# AB2KController.net
KiCad netlist of a schematic drawn in EAGLE
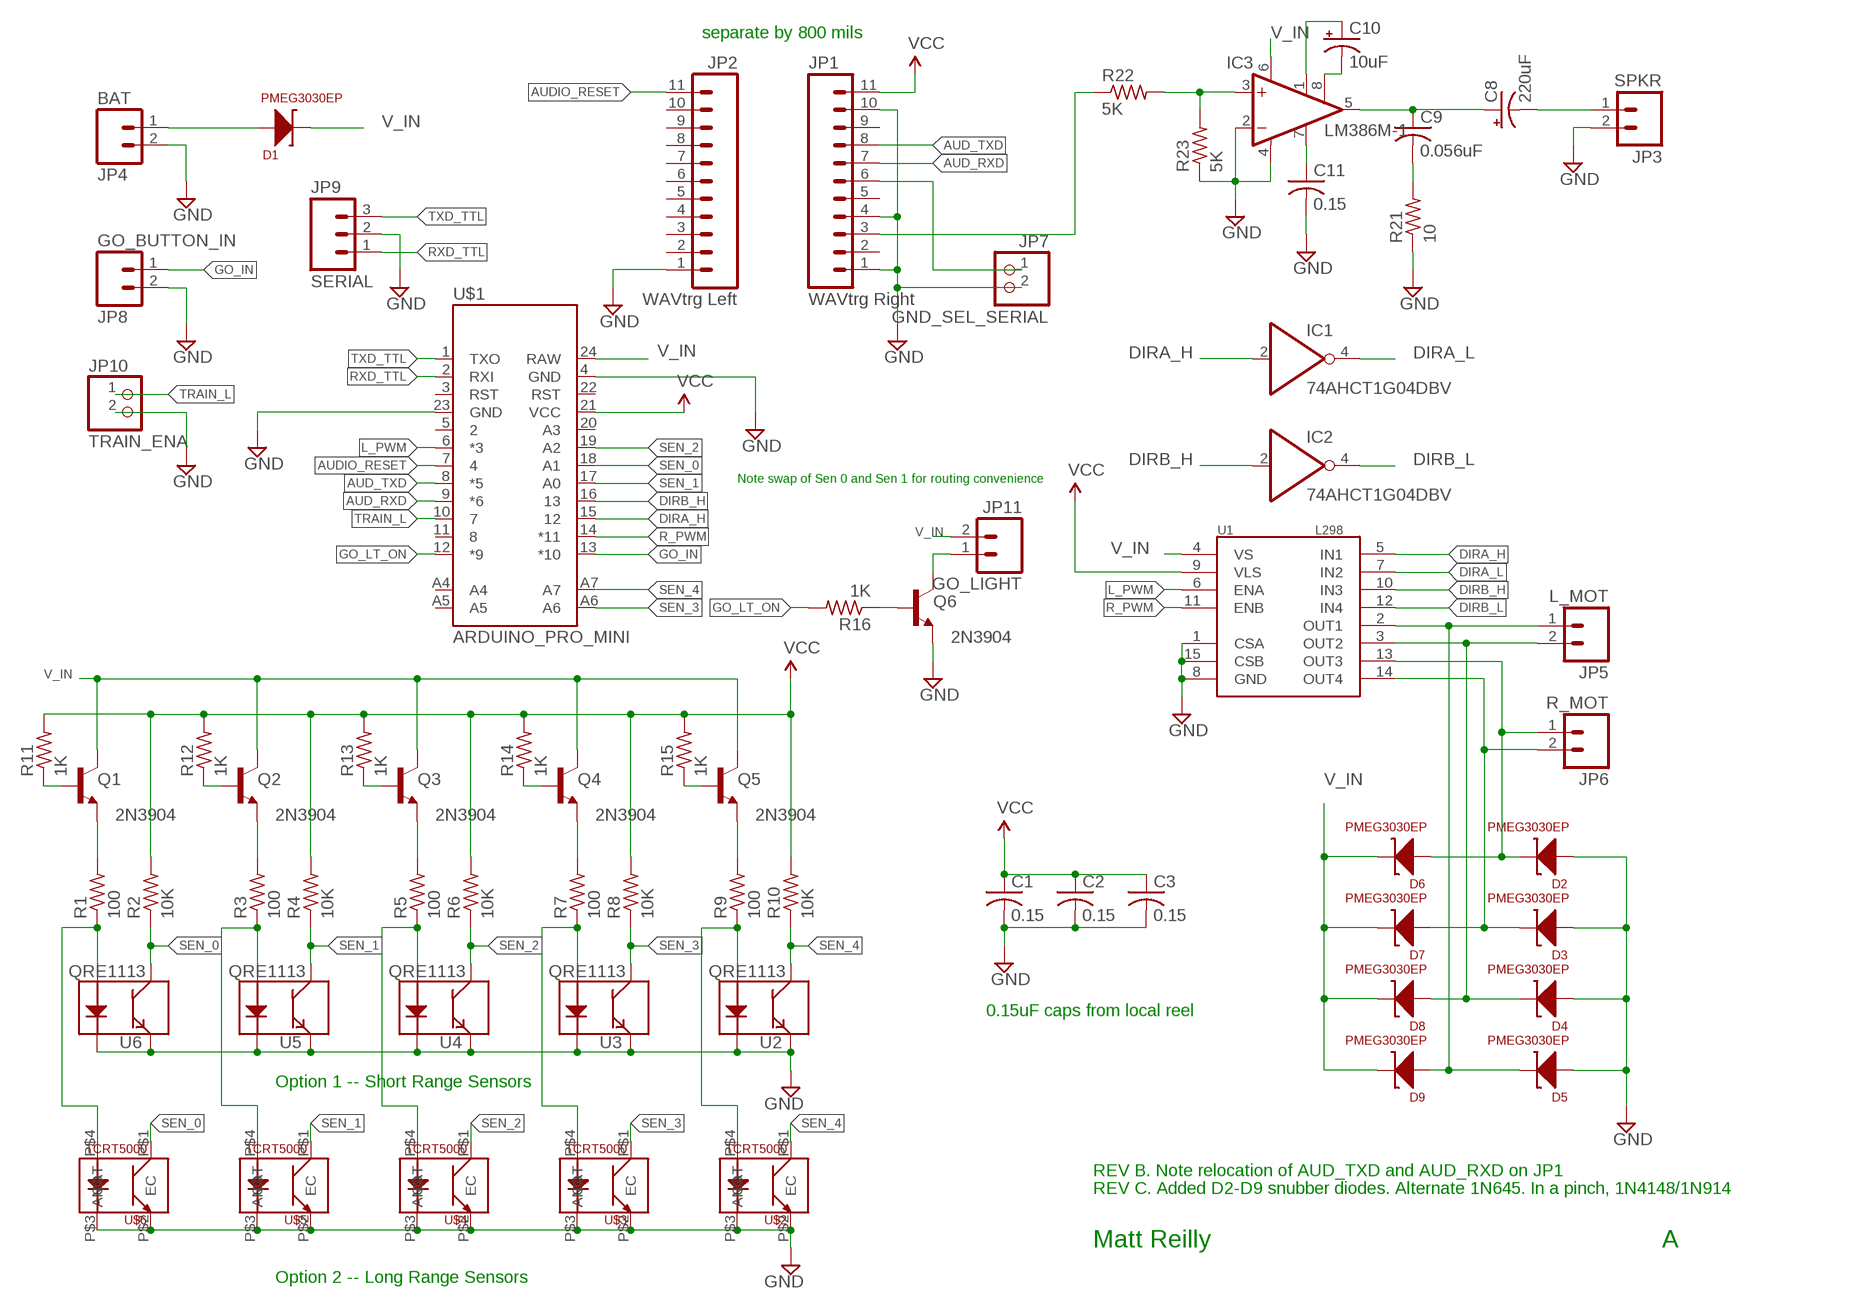
[diagram p0: schematic, sheet 1]

(export (version "E")
  (design (tool "Eeschema 10.0.6"))
  (components
    (comp (ref "C1")
      (value "0.15")
      (footprint "eagle-import:C1206K")
      (libsource (lib "eagle-import") (part "resistor_C-USC1206K"))
    )
    (comp (ref "C2")
      (value "0.15")
      (footprint "eagle-import:C1206K")
      (libsource (lib "eagle-import") (part "resistor_C-USC1206K"))
    )
    (comp (ref "C3")
      (value "0.15")
      (footprint "eagle-import:C1206K")
      (libsource (lib "eagle-import") (part "resistor_C-USC1206K"))
    )
    (comp (ref "C8")
      (value "220uF")
      (footprint "eagle-import:D_7343-31R")
      (libsource (lib "eagle-import") (part "CPOL-USD/7343-31R"))
    )
    (comp (ref "C9")
      (value "0.056uF")
      (footprint "eagle-import:C1210")
      (libsource (lib "eagle-import") (part "C-USC1210"))
    )
    (comp (ref "C10")
      (value "10uF")
      (footprint "eagle-import:D_7343-31R")
      (libsource (lib "eagle-import") (part "CPOL-USD/7343-31R"))
    )
    (comp (ref "C11")
      (value "0.15")
      (footprint "eagle-import:C1206K")
      (libsource (lib "eagle-import") (part "resistor_C-USC1206K"))
    )
    (comp (ref "D1")
      (value "PMEG3030EP")
      (footprint "eagle-import:SOD128")
      (libsource (lib "eagle-import") (part "PMEG3030EP"))
    )
    (comp (ref "D2")
      (value "PMEG3030EP")
      (footprint "eagle-import:SOD128")
      (libsource (lib "eagle-import") (part "PMEG3030EP"))
    )
    (comp (ref "D3")
      (value "PMEG3030EP")
      (footprint "eagle-import:SOD128")
      (libsource (lib "eagle-import") (part "PMEG3030EP"))
    )
    (comp (ref "D4")
      (value "PMEG3030EP")
      (footprint "eagle-import:SOD128")
      (libsource (lib "eagle-import") (part "PMEG3030EP"))
    )
    (comp (ref "D5")
      (value "PMEG3030EP")
      (footprint "eagle-import:SOD128")
      (libsource (lib "eagle-import") (part "PMEG3030EP"))
    )
    (comp (ref "D6")
      (value "PMEG3030EP")
      (footprint "eagle-import:SOD128")
      (libsource (lib "eagle-import") (part "PMEG3030EP"))
    )
    (comp (ref "D7")
      (value "PMEG3030EP")
      (footprint "eagle-import:SOD128")
      (libsource (lib "eagle-import") (part "PMEG3030EP"))
    )
    (comp (ref "D8")
      (value "PMEG3030EP")
      (footprint "eagle-import:SOD128")
      (libsource (lib "eagle-import") (part "PMEG3030EP"))
    )
    (comp (ref "D9")
      (value "PMEG3030EP")
      (footprint "eagle-import:SOD128")
      (libsource (lib "eagle-import") (part "PMEG3030EP"))
    )
    (comp (ref "IC1")
      (value "74AHCT1G04DBV")
      (footprint "eagle-import:SOT23-5")
      (libsource (lib "eagle-import") (part "741G04DBVAHCT"))
    )
    (comp (ref "IC2")
      (value "74AHCT1G04DBV")
      (footprint "eagle-import:SOT23-5")
      (libsource (lib "eagle-import") (part "741G04DBVAHCT"))
    )
    (comp (ref "IC3")
      (value "LM386M-1")
      (footprint "eagle-import:SO08")
      (libsource (lib "eagle-import") (part "LM386?-M1"))
    )
    (comp (ref "JP1")
      (value "WAVtrg Right")
      (footprint "eagle-import:1X11")
      (libsource (lib "eagle-import") (part "M11PTH"))
    )
    (comp (ref "JP2")
      (value "WAVtrg Left")
      (footprint "eagle-import:1X11")
      (libsource (lib "eagle-import") (part "M11PTH"))
    )
    (comp (ref "JP3")
      (value "SPKR")
      (footprint "eagle-import:SCREWTERMINAL-5MM-2")
      (libsource (lib "eagle-import") (part "M025MM"))
    )
    (comp (ref "JP4")
      (value "BAT")
      (footprint "eagle-import:SCREWTERMINAL-5MM-2")
      (libsource (lib "eagle-import") (part "M025MM"))
    )
    (comp (ref "JP5")
      (value "L_MOT")
      (footprint "eagle-import:SCREWTERMINAL-5MM-2")
      (libsource (lib "eagle-import") (part "M025MM"))
    )
    (comp (ref "JP6")
      (value "R_MOT")
      (footprint "eagle-import:SCREWTERMINAL-5MM-2")
      (libsource (lib "eagle-import") (part "M025MM"))
    )
    (comp (ref "JP7")
      (value "GND_SEL_SERIAL")
      (footprint "eagle-import:1X02")
      (libsource (lib "eagle-import") (part "PINHD-1X2"))
    )
    (comp (ref "JP8")
      (value "GO_BUTTON_IN")
      (footprint "eagle-import:SCREWTERMINAL-5MM-2")
      (libsource (lib "eagle-import") (part "M025MM"))
    )
    (comp (ref "JP9")
      (value "SERIAL")
      (footprint "eagle-import:1X03")
      (libsource (lib "eagle-import") (part "M03PTH"))
    )
    (comp (ref "JP10")
      (value "TRAIN_ENA")
      (footprint "eagle-import:1X02")
      (libsource (lib "eagle-import") (part "PINHD-1X2"))
    )
    (comp (ref "JP11")
      (value "GO_LIGHT")
      (footprint "eagle-import:SCREWTERMINAL-5MM-2")
      (libsource (lib "eagle-import") (part "M025MM"))
    )
    (comp (ref "Q1")
      (value "2N3904")
      (footprint "eagle-import:TO92")
      (libsource (lib "eagle-import") (part "2N3904"))
    )
    (comp (ref "Q2")
      (value "2N3904")
      (footprint "eagle-import:TO92")
      (libsource (lib "eagle-import") (part "2N3904"))
    )
    (comp (ref "Q3")
      (value "2N3904")
      (footprint "eagle-import:TO92")
      (libsource (lib "eagle-import") (part "2N3904"))
    )
    (comp (ref "Q4")
      (value "2N3904")
      (footprint "eagle-import:TO92")
      (libsource (lib "eagle-import") (part "2N3904"))
    )
    (comp (ref "Q5")
      (value "2N3904")
      (footprint "eagle-import:TO92")
      (libsource (lib "eagle-import") (part "2N3904"))
    )
    (comp (ref "Q6")
      (value "2N3904")
      (footprint "eagle-import:TO92")
      (libsource (lib "eagle-import") (part "2N3904"))
    )
    (comp (ref "R1")
      (value "100")
      (footprint "eagle-import:M1206")
      (libsource (lib "eagle-import") (part "resistor_R-US_M1206"))
    )
    (comp (ref "R2")
      (value "10K")
      (footprint "eagle-import:M1206")
      (libsource (lib "eagle-import") (part "resistor_R-US_M1206"))
    )
    (comp (ref "R3")
      (value "100")
      (footprint "eagle-import:M1206")
      (libsource (lib "eagle-import") (part "resistor_R-US_M1206"))
    )
    (comp (ref "R4")
      (value "10K")
      (footprint "eagle-import:M1206")
      (libsource (lib "eagle-import") (part "resistor_R-US_M1206"))
    )
    (comp (ref "R5")
      (value "100")
      (footprint "eagle-import:M1206")
      (libsource (lib "eagle-import") (part "resistor_R-US_M1206"))
    )
    (comp (ref "R6")
      (value "10K")
      (footprint "eagle-import:M1206")
      (libsource (lib "eagle-import") (part "resistor_R-US_M1206"))
    )
    (comp (ref "R7")
      (value "100")
      (footprint "eagle-import:M1206")
      (libsource (lib "eagle-import") (part "resistor_R-US_M1206"))
    )
    (comp (ref "R8")
      (value "10K")
      (footprint "eagle-import:M1206")
      (libsource (lib "eagle-import") (part "resistor_R-US_M1206"))
    )
    (comp (ref "R9")
      (value "100")
      (footprint "eagle-import:M1206")
      (libsource (lib "eagle-import") (part "resistor_R-US_M1206"))
    )
    (comp (ref "R10")
      (value "10K")
      (footprint "eagle-import:M1206")
      (libsource (lib "eagle-import") (part "resistor_R-US_M1206"))
    )
    (comp (ref "R11")
      (value "1K")
      (footprint "eagle-import:M1206")
      (libsource (lib "eagle-import") (part "resistor_R-US_M1206"))
    )
    (comp (ref "R12")
      (value "1K")
      (footprint "eagle-import:M1206")
      (libsource (lib "eagle-import") (part "resistor_R-US_M1206"))
    )
    (comp (ref "R13")
      (value "1K")
      (footprint "eagle-import:M1206")
      (libsource (lib "eagle-import") (part "resistor_R-US_M1206"))
    )
    (comp (ref "R14")
      (value "1K")
      (footprint "eagle-import:M1206")
      (libsource (lib "eagle-import") (part "resistor_R-US_M1206"))
    )
    (comp (ref "R15")
      (value "1K")
      (footprint "eagle-import:M1206")
      (libsource (lib "eagle-import") (part "resistor_R-US_M1206"))
    )
    (comp (ref "R16")
      (value "1K")
      (footprint "eagle-import:M1206")
      (libsource (lib "eagle-import") (part "resistor_R-US_M1206"))
    )
    (comp (ref "R21")
      (value "10")
      (footprint "eagle-import:R1210")
      (libsource (lib "eagle-import") (part "R-US_R1210"))
    )
    (comp (ref "R22")
      (value "5K")
      (footprint "eagle-import:R1206")
      (libsource (lib "eagle-import") (part "R-US_R1206"))
    )
    (comp (ref "R23")
      (value "5K")
      (footprint "eagle-import:R1206")
      (libsource (lib "eagle-import") (part "R-US_R1206"))
    )
    (comp (ref "U$1")
      (value "ARDUINO_PRO_MINI")
      (footprint "eagle-import:ARDUINO_PRO_MINI")
      (libsource (lib "eagle-import") (part "ARDUINO_PRO_MINI"))
    )
    (comp (ref "U$2")
      (value "TCRT5000")
      (footprint "eagle-import:TCRT5000")
      (libsource (lib "eagle-import") (part "TCRT5000"))
    )
    (comp (ref "U$3")
      (value "TCRT5000")
      (footprint "eagle-import:TCRT5000")
      (libsource (lib "eagle-import") (part "TCRT5000"))
    )
    (comp (ref "U$4")
      (value "TCRT5000")
      (footprint "eagle-import:TCRT5000")
      (libsource (lib "eagle-import") (part "TCRT5000"))
    )
    (comp (ref "U$5")
      (value "TCRT5000")
      (footprint "eagle-import:TCRT5000")
      (libsource (lib "eagle-import") (part "TCRT5000"))
    )
    (comp (ref "U$6")
      (value "TCRT5000")
      (footprint "eagle-import:TCRT5000")
      (libsource (lib "eagle-import") (part "TCRT5000"))
    )
    (comp (ref "U1")
      (value "L298")
      (footprint "eagle-import:MULTIWATT15")
      (libsource (lib "eagle-import") (part "L298"))
    )
    (comp (ref "U2")
      (value "QRE1113")
      (footprint "eagle-import:QRE1113")
      (libsource (lib "eagle-import") (part "QRE1113"))
    )
    (comp (ref "U3")
      (value "QRE1113")
      (footprint "eagle-import:QRE1113")
      (libsource (lib "eagle-import") (part "QRE1113"))
    )
    (comp (ref "U4")
      (value "QRE1113")
      (footprint "eagle-import:QRE1113")
      (libsource (lib "eagle-import") (part "QRE1113"))
    )
    (comp (ref "U5")
      (value "QRE1113")
      (footprint "eagle-import:QRE1113")
      (libsource (lib "eagle-import") (part "QRE1113"))
    )
    (comp (ref "U6")
      (value "QRE1113")
      (footprint "eagle-import:QRE1113")
      (libsource (lib "eagle-import") (part "QRE1113"))
    )
  )
  (nets
    (net (code "1") (name "/V_IN") (class "Default")
      (node (ref "D1") (pin "P$2") (pinfunction "C_P$2") (pintype "bidirectional"))
      (node (ref "D6") (pin "P$2") (pinfunction "C_P$2") (pintype "bidirectional"))
      (node (ref "D7") (pin "P$2") (pinfunction "C_P$2") (pintype "bidirectional"))
      (node (ref "D8") (pin "P$2") (pinfunction "C_P$2") (pintype "bidirectional"))
      (node (ref "D9") (pin "P$2") (pinfunction "C_P$2") (pintype "bidirectional"))
      (node (ref "IC3") (pin "6") (pinfunction "VS_6") (pintype "power_in"))
      (node (ref "JP11") (pin "2") (pinfunction "2_2") (pintype "passive"))
      (node (ref "Q1") (pin "1") (pinfunction "C_1") (pintype "passive"))
      (node (ref "Q2") (pin "1") (pinfunction "C_1") (pintype "passive"))
      (node (ref "Q3") (pin "1") (pinfunction "C_1") (pintype "passive"))
      (node (ref "Q4") (pin "1") (pinfunction "C_1") (pintype "passive"))
      (node (ref "Q5") (pin "1") (pinfunction "C_1") (pintype "passive"))
      (node (ref "U$1") (pin "24") (pinfunction "RAW_24") (pintype "bidirectional"))
      (node (ref "U1") (pin "4") (pinfunction "VS_4") (pintype "bidirectional"))
    )
    (net (code "2") (name "AUDIO_RESET") (class "Default")
      (node (ref "JP2") (pin "11") (pinfunction "11_11") (pintype "passive"))
      (node (ref "U$1") (pin "7") (pinfunction "4_7") (pintype "bidirectional"))
    )
    (net (code "3") (name "AUD_RXD") (class "Default")
      (node (ref "JP1") (pin "7") (pinfunction "7_7") (pintype "passive"))
      (node (ref "U$1") (pin "9") (pinfunction "*6_9") (pintype "bidirectional"))
    )
    (net (code "4") (name "AUD_TXD") (class "Default")
      (node (ref "JP1") (pin "8") (pinfunction "8_8") (pintype "passive"))
      (node (ref "U$1") (pin "8") (pinfunction "*5_8") (pintype "bidirectional"))
    )
    (net (code "5") (name "DIRA_H") (class "Default")
      (node (ref "IC1") (pin "2") (pinfunction "I_2") (pintype "input"))
      (node (ref "U$1") (pin "15") (pinfunction "12_15") (pintype "bidirectional"))
      (node (ref "U1") (pin "5") (pinfunction "IN1_5") (pintype "bidirectional"))
    )
    (net (code "6") (name "DIRA_L") (class "Default")
      (node (ref "IC1") (pin "4") (pinfunction "O_4") (pintype "output"))
      (node (ref "U1") (pin "7") (pinfunction "IN2_7") (pintype "bidirectional"))
    )
    (net (code "7") (name "DIRB_H") (class "Default")
      (node (ref "IC2") (pin "2") (pinfunction "I_2") (pintype "input"))
      (node (ref "U$1") (pin "16") (pinfunction "13_16") (pintype "bidirectional"))
      (node (ref "U1") (pin "10") (pinfunction "IN3_10") (pintype "bidirectional"))
    )
    (net (code "8") (name "DIRB_L") (class "Default")
      (node (ref "IC2") (pin "4") (pinfunction "O_4") (pintype "output"))
      (node (ref "U1") (pin "12") (pinfunction "IN4_12") (pintype "bidirectional"))
    )
    (net (code "9") (name "GND") (class "Default")
      (node (ref "C1") (pin "2") (pinfunction "2_2") (pintype "passive"))
      (node (ref "C11") (pin "2") (pinfunction "2_2") (pintype "passive"))
      (node (ref "C2") (pin "2") (pinfunction "2_2") (pintype "passive"))
      (node (ref "C3") (pin "2") (pinfunction "2_2") (pintype "passive"))
      (node (ref "D2") (pin "P$1") (pinfunction "A_P$1") (pintype "bidirectional"))
      (node (ref "D3") (pin "P$1") (pinfunction "A_P$1") (pintype "bidirectional"))
      (node (ref "D4") (pin "P$1") (pinfunction "A_P$1") (pintype "bidirectional"))
      (node (ref "D5") (pin "P$1") (pinfunction "A_P$1") (pintype "bidirectional"))
      (node (ref "IC3") (pin "2") (pinfunction "-IN_2") (pintype "input"))
      (node (ref "IC3") (pin "4") (pinfunction "GND_4") (pintype "power_in"))
      (node (ref "JP1") (pin "1") (pinfunction "1_1") (pintype "passive"))
      (node (ref "JP1") (pin "10") (pinfunction "10_10") (pintype "passive"))
      (node (ref "JP1") (pin "4") (pinfunction "4_4") (pintype "passive"))
      (node (ref "JP10") (pin "2") (pinfunction "2_2") (pintype "passive"))
      (node (ref "JP2") (pin "1") (pinfunction "1_1") (pintype "passive"))
      (node (ref "JP3") (pin "2") (pinfunction "2_2") (pintype "passive"))
      (node (ref "JP4") (pin "2") (pinfunction "2_2") (pintype "passive"))
      (node (ref "JP7") (pin "2") (pinfunction "2_2") (pintype "passive"))
      (node (ref "JP8") (pin "2") (pinfunction "2_2") (pintype "passive"))
      (node (ref "JP9") (pin "2") (pinfunction "2_2") (pintype "passive"))
      (node (ref "Q6") (pin "3") (pinfunction "E_3") (pintype "passive"))
      (node (ref "R21") (pin "1") (pinfunction "1_1") (pintype "passive"))
      (node (ref "R23") (pin "1") (pinfunction "1_1") (pintype "passive"))
      (node (ref "U$1") (pin "23") (pinfunction "GND_23") (pintype "bidirectional"))
      (node (ref "U$1") (pin "4") (pinfunction "GND_4") (pintype "bidirectional"))
      (node (ref "U$2") (pin "P$2") (pinfunction "E_P$2") (pintype "bidirectional"))
      (node (ref "U$2") (pin "P$3") (pinfunction "CAT_P$3") (pintype "bidirectional"))
      (node (ref "U$3") (pin "P$2") (pinfunction "E_P$2") (pintype "bidirectional"))
      (node (ref "U$3") (pin "P$3") (pinfunction "CAT_P$3") (pintype "bidirectional"))
      (node (ref "U$4") (pin "P$2") (pinfunction "E_P$2") (pintype "bidirectional"))
      (node (ref "U$4") (pin "P$3") (pinfunction "CAT_P$3") (pintype "bidirectional"))
      (node (ref "U$5") (pin "P$2") (pinfunction "E_P$2") (pintype "bidirectional"))
      (node (ref "U$5") (pin "P$3") (pinfunction "CAT_P$3") (pintype "bidirectional"))
      (node (ref "U$6") (pin "P$2") (pinfunction "E_P$2") (pintype "bidirectional"))
      (node (ref "U$6") (pin "P$3") (pinfunction "CAT_P$3") (pintype "bidirectional"))
      (node (ref "U1") (pin "1") (pinfunction "CSA_1") (pintype "bidirectional"))
      (node (ref "U1") (pin "15") (pinfunction "CSB_15") (pintype "bidirectional"))
      (node (ref "U1") (pin "8") (pinfunction "GND_8") (pintype "bidirectional"))
      (node (ref "U2") (pin "2") (pinfunction "K_2") (pintype "bidirectional"))
      (node (ref "U2") (pin "4") (pinfunction "E_4") (pintype "bidirectional"))
      (node (ref "U3") (pin "2") (pinfunction "K_2") (pintype "bidirectional"))
      (node (ref "U3") (pin "4") (pinfunction "E_4") (pintype "bidirectional"))
      (node (ref "U4") (pin "2") (pinfunction "K_2") (pintype "bidirectional"))
      (node (ref "U4") (pin "4") (pinfunction "E_4") (pintype "bidirectional"))
      (node (ref "U5") (pin "2") (pinfunction "K_2") (pintype "bidirectional"))
      (node (ref "U5") (pin "4") (pinfunction "E_4") (pintype "bidirectional"))
      (node (ref "U6") (pin "2") (pinfunction "K_2") (pintype "bidirectional"))
      (node (ref "U6") (pin "4") (pinfunction "E_4") (pintype "bidirectional"))
    )
    (net (code "10") (name "GO_IN") (class "Default")
      (node (ref "JP8") (pin "1") (pinfunction "1_1") (pintype "passive"))
      (node (ref "U$1") (pin "13") (pinfunction "*10_13") (pintype "bidirectional"))
    )
    (net (code "11") (name "GO_LT_ON") (class "Default")
      (node (ref "R16") (pin "2") (pinfunction "2_2") (pintype "passive"))
      (node (ref "U$1") (pin "12") (pinfunction "*9_12") (pintype "bidirectional"))
    )
    (net (code "12") (name "L_PWM") (class "Default")
      (node (ref "U$1") (pin "6") (pinfunction "*3_6") (pintype "bidirectional"))
      (node (ref "U1") (pin "6") (pinfunction "ENA_6") (pintype "bidirectional"))
    )
    (net (code "13") (name "Net-(C8-Pad-)") (class "Default")
      (node (ref "C8") (pin "-") (pinfunction "-_-") (pintype "passive"))
      (node (ref "JP3") (pin "1") (pinfunction "1_1") (pintype "passive"))
    )
    (net (code "14") (name "Net-(C9-Pad2)") (class "Default")
      (node (ref "C9") (pin "2") (pinfunction "2_2") (pintype "passive"))
      (node (ref "R21") (pin "2") (pinfunction "2_2") (pintype "passive"))
    )
    (net (code "15") (name "Net-(C10-Pad+)") (class "Default")
      (node (ref "C10") (pin "+") (pinfunction "+_+") (pintype "passive"))
      (node (ref "IC3") (pin "1") (pinfunction "GAIN_1") (pintype "passive"))
    )
    (net (code "16") (name "Net-(C10-Pad-)") (class "Default")
      (node (ref "C10") (pin "-") (pinfunction "-_-") (pintype "passive"))
      (node (ref "IC3") (pin "8") (pinfunction "GAIN_8") (pintype "passive"))
    )
    (net (code "17") (name "Net-(D1-A)") (class "Default")
      (node (ref "D1") (pin "P$1") (pinfunction "A_P$1") (pintype "bidirectional"))
      (node (ref "JP4") (pin "1") (pinfunction "1_1") (pintype "passive"))
    )
    (net (code "18") (name "Net-(D2-C)") (class "Default")
      (node (ref "D2") (pin "P$2") (pinfunction "C_P$2") (pintype "bidirectional"))
      (node (ref "D6") (pin "P$1") (pinfunction "A_P$1") (pintype "bidirectional"))
      (node (ref "JP6") (pin "1") (pinfunction "1_1") (pintype "passive"))
      (node (ref "U1") (pin "13") (pinfunction "OUT3_13") (pintype "bidirectional"))
    )
    (net (code "19") (name "Net-(D3-C)") (class "Default")
      (node (ref "D3") (pin "P$2") (pinfunction "C_P$2") (pintype "bidirectional"))
      (node (ref "D7") (pin "P$1") (pinfunction "A_P$1") (pintype "bidirectional"))
      (node (ref "JP6") (pin "2") (pinfunction "2_2") (pintype "passive"))
      (node (ref "U1") (pin "14") (pinfunction "OUT4_14") (pintype "bidirectional"))
    )
    (net (code "20") (name "Net-(D4-C)") (class "Default")
      (node (ref "D4") (pin "P$2") (pinfunction "C_P$2") (pintype "bidirectional"))
      (node (ref "D8") (pin "P$1") (pinfunction "A_P$1") (pintype "bidirectional"))
      (node (ref "JP5") (pin "2") (pinfunction "2_2") (pintype "passive"))
      (node (ref "U1") (pin "3") (pinfunction "OUT2_3") (pintype "bidirectional"))
    )
    (net (code "21") (name "Net-(D5-C)") (class "Default")
      (node (ref "D5") (pin "P$2") (pinfunction "C_P$2") (pintype "bidirectional"))
      (node (ref "D9") (pin "P$1") (pinfunction "A_P$1") (pintype "bidirectional"))
      (node (ref "JP5") (pin "1") (pinfunction "1_1") (pintype "passive"))
      (node (ref "U1") (pin "2") (pinfunction "OUT1_2") (pintype "bidirectional"))
    )
    (net (code "22") (name "Net-(IC3-+IN)") (class "Default")
      (node (ref "IC3") (pin "3") (pinfunction "+IN_3") (pintype "input"))
      (node (ref "R22") (pin "2") (pinfunction "2_2") (pintype "passive"))
      (node (ref "R23") (pin "2") (pinfunction "2_2") (pintype "passive"))
    )
    (net (code "23") (name "Net-(IC3-BYPASS)") (class "Default")
      (node (ref "C11") (pin "1") (pinfunction "1_1") (pintype "passive"))
      (node (ref "IC3") (pin "7") (pinfunction "BYPASS_7") (pintype "passive"))
    )
    (net (code "24") (name "Net-(IC3-OUT)") (class "Default")
      (node (ref "C8") (pin "+") (pinfunction "+_+") (pintype "passive"))
      (node (ref "C9") (pin "1") (pinfunction "1_1") (pintype "passive"))
      (node (ref "IC3") (pin "5") (pinfunction "OUT_5") (pintype "output"))
    )
    (net (code "25") (name "Net-(JP1-Pad3)") (class "Default")
      (node (ref "JP1") (pin "3") (pinfunction "3_3") (pintype "passive"))
      (node (ref "R22") (pin "1") (pinfunction "1_1") (pintype "passive"))
    )
    (net (code "26") (name "Net-(JP1-Pad6)") (class "Default")
      (node (ref "JP1") (pin "6") (pinfunction "6_6") (pintype "passive"))
      (node (ref "JP7") (pin "1") (pinfunction "1_1") (pintype "passive"))
    )
    (net (code "27") (name "Net-(Q1-B)") (class "Default")
      (node (ref "Q1") (pin "2") (pinfunction "B_2") (pintype "passive"))
      (node (ref "R11") (pin "1") (pinfunction "1_1") (pintype "passive"))
    )
    (net (code "28") (name "Net-(Q1-E)") (class "Default")
      (node (ref "Q1") (pin "3") (pinfunction "E_3") (pintype "passive"))
      (node (ref "R1") (pin "2") (pinfunction "2_2") (pintype "passive"))
    )
    (net (code "29") (name "Net-(Q2-B)") (class "Default")
      (node (ref "Q2") (pin "2") (pinfunction "B_2") (pintype "passive"))
      (node (ref "R12") (pin "1") (pinfunction "1_1") (pintype "passive"))
    )
    (net (code "30") (name "Net-(Q2-E)") (class "Default")
      (node (ref "Q2") (pin "3") (pinfunction "E_3") (pintype "passive"))
      (node (ref "R3") (pin "2") (pinfunction "2_2") (pintype "passive"))
    )
    (net (code "31") (name "Net-(Q3-B)") (class "Default")
      (node (ref "Q3") (pin "2") (pinfunction "B_2") (pintype "passive"))
      (node (ref "R13") (pin "1") (pinfunction "1_1") (pintype "passive"))
    )
    (net (code "32") (name "Net-(Q3-E)") (class "Default")
      (node (ref "Q3") (pin "3") (pinfunction "E_3") (pintype "passive"))
      (node (ref "R5") (pin "2") (pinfunction "2_2") (pintype "passive"))
    )
    (net (code "33") (name "Net-(Q4-B)") (class "Default")
      (node (ref "Q4") (pin "2") (pinfunction "B_2") (pintype "passive"))
      (node (ref "R14") (pin "1") (pinfunction "1_1") (pintype "passive"))
    )
    (net (code "34") (name "Net-(Q4-E)") (class "Default")
      (node (ref "Q4") (pin "3") (pinfunction "E_3") (pintype "passive"))
      (node (ref "R7") (pin "2") (pinfunction "2_2") (pintype "passive"))
    )
    (net (code "35") (name "Net-(Q5-B)") (class "Default")
      (node (ref "Q5") (pin "2") (pinfunction "B_2") (pintype "passive"))
      (node (ref "R15") (pin "1") (pinfunction "1_1") (pintype "passive"))
    )
    (net (code "36") (name "Net-(Q5-E)") (class "Default")
      (node (ref "Q5") (pin "3") (pinfunction "E_3") (pintype "passive"))
      (node (ref "R9") (pin "2") (pinfunction "2_2") (pintype "passive"))
    )
    (net (code "37") (name "Net-(Q6-B)") (class "Default")
      (node (ref "Q6") (pin "2") (pinfunction "B_2") (pintype "passive"))
      (node (ref "R16") (pin "1") (pinfunction "1_1") (pintype "passive"))
    )
    (net (code "38") (name "Net-(Q6-C)") (class "Default")
      (node (ref "JP11") (pin "1") (pinfunction "1_1") (pintype "passive"))
      (node (ref "Q6") (pin "1") (pinfunction "C_1") (pintype "passive"))
    )
    (net (code "39") (name "Net-(U$2-ANO)") (class "Default")
      (node (ref "R9") (pin "1") (pinfunction "1_1") (pintype "passive"))
      (node (ref "U$2") (pin "P$4") (pinfunction "ANO_P$4") (pintype "bidirectional"))
      (node (ref "U2") (pin "1") (pinfunction "A_1") (pintype "bidirectional"))
    )
    (net (code "40") (name "Net-(U$3-ANO)") (class "Default")
      (node (ref "R7") (pin "1") (pinfunction "1_1") (pintype "passive"))
      (node (ref "U$3") (pin "P$4") (pinfunction "ANO_P$4") (pintype "bidirectional"))
      (node (ref "U3") (pin "1") (pinfunction "A_1") (pintype "bidirectional"))
    )
    (net (code "41") (name "Net-(U$4-ANO)") (class "Default")
      (node (ref "R5") (pin "1") (pinfunction "1_1") (pintype "passive"))
      (node (ref "U$4") (pin "P$4") (pinfunction "ANO_P$4") (pintype "bidirectional"))
      (node (ref "U4") (pin "1") (pinfunction "A_1") (pintype "bidirectional"))
    )
    (net (code "42") (name "Net-(U$5-ANO)") (class "Default")
      (node (ref "R3") (pin "1") (pinfunction "1_1") (pintype "passive"))
      (node (ref "U$5") (pin "P$4") (pinfunction "ANO_P$4") (pintype "bidirectional"))
      (node (ref "U5") (pin "1") (pinfunction "A_1") (pintype "bidirectional"))
    )
    (net (code "43") (name "Net-(U$6-ANO)") (class "Default")
      (node (ref "R1") (pin "1") (pinfunction "1_1") (pintype "passive"))
      (node (ref "U$6") (pin "P$4") (pinfunction "ANO_P$4") (pintype "bidirectional"))
      (node (ref "U6") (pin "1") (pinfunction "A_1") (pintype "bidirectional"))
    )
    (net (code "44") (name "RXD_TTL") (class "Default")
      (node (ref "JP9") (pin "1") (pinfunction "1_1") (pintype "passive"))
      (node (ref "U$1") (pin "2") (pinfunction "RXI_2") (pintype "bidirectional"))
    )
    (net (code "45") (name "R_PWM") (class "Default")
      (node (ref "U$1") (pin "14") (pinfunction "*11_14") (pintype "bidirectional"))
      (node (ref "U1") (pin "11") (pinfunction "ENB_11") (pintype "bidirectional"))
    )
    (net (code "46") (name "SEN_0") (class "Default")
      (node (ref "R2") (pin "1") (pinfunction "1_1") (pintype "passive"))
      (node (ref "U$1") (pin "18") (pinfunction "A1_18") (pintype "bidirectional"))
      (node (ref "U$6") (pin "P$1") (pinfunction "C_P$1") (pintype "bidirectional"))
      (node (ref "U6") (pin "3") (pinfunction "C_3") (pintype "bidirectional"))
    )
    (net (code "47") (name "SEN_1") (class "Default")
      (node (ref "R4") (pin "1") (pinfunction "1_1") (pintype "passive"))
      (node (ref "U$1") (pin "17") (pinfunction "A0_17") (pintype "bidirectional"))
      (node (ref "U$5") (pin "P$1") (pinfunction "C_P$1") (pintype "bidirectional"))
      (node (ref "U5") (pin "3") (pinfunction "C_3") (pintype "bidirectional"))
    )
    (net (code "48") (name "SEN_2") (class "Default")
      (node (ref "R6") (pin "1") (pinfunction "1_1") (pintype "passive"))
      (node (ref "U$1") (pin "19") (pinfunction "A2_19") (pintype "bidirectional"))
      (node (ref "U$4") (pin "P$1") (pinfunction "C_P$1") (pintype "bidirectional"))
      (node (ref "U4") (pin "3") (pinfunction "C_3") (pintype "bidirectional"))
    )
    (net (code "49") (name "SEN_3") (class "Default")
      (node (ref "R8") (pin "1") (pinfunction "1_1") (pintype "passive"))
      (node (ref "U$1") (pin "A6") (pinfunction "A6_A6") (pintype "bidirectional"))
      (node (ref "U$3") (pin "P$1") (pinfunction "C_P$1") (pintype "bidirectional"))
      (node (ref "U3") (pin "3") (pinfunction "C_3") (pintype "bidirectional"))
    )
    (net (code "50") (name "SEN_4") (class "Default")
      (node (ref "R10") (pin "1") (pinfunction "1_1") (pintype "passive"))
      (node (ref "U$1") (pin "A7") (pinfunction "A7_A7") (pintype "bidirectional"))
      (node (ref "U$2") (pin "P$1") (pinfunction "C_P$1") (pintype "bidirectional"))
      (node (ref "U2") (pin "3") (pinfunction "C_3") (pintype "bidirectional"))
    )
    (net (code "51") (name "TRAIN_L") (class "Default")
      (node (ref "JP10") (pin "1") (pinfunction "1_1") (pintype "passive"))
      (node (ref "U$1") (pin "10") (pinfunction "7_10") (pintype "bidirectional"))
    )
    (net (code "52") (name "TXD_TTL") (class "Default")
      (node (ref "JP9") (pin "3") (pinfunction "3_3") (pintype "passive"))
      (node (ref "U$1") (pin "1") (pinfunction "TXO_1") (pintype "bidirectional"))
    )
    (net (code "53") (name "VCC") (class "Default")
      (node (ref "C1") (pin "1") (pinfunction "1_1") (pintype "passive"))
      (node (ref "C2") (pin "1") (pinfunction "1_1") (pintype "passive"))
      (node (ref "C3") (pin "1") (pinfunction "1_1") (pintype "passive"))
      (node (ref "JP1") (pin "11") (pinfunction "11_11") (pintype "passive"))
      (node (ref "R10") (pin "2") (pinfunction "2_2") (pintype "passive"))
      (node (ref "R11") (pin "2") (pinfunction "2_2") (pintype "passive"))
      (node (ref "R12") (pin "2") (pinfunction "2_2") (pintype "passive"))
      (node (ref "R13") (pin "2") (pinfunction "2_2") (pintype "passive"))
      (node (ref "R14") (pin "2") (pinfunction "2_2") (pintype "passive"))
      (node (ref "R15") (pin "2") (pinfunction "2_2") (pintype "passive"))
      (node (ref "R2") (pin "2") (pinfunction "2_2") (pintype "passive"))
      (node (ref "R4") (pin "2") (pinfunction "2_2") (pintype "passive"))
      (node (ref "R6") (pin "2") (pinfunction "2_2") (pintype "passive"))
      (node (ref "R8") (pin "2") (pinfunction "2_2") (pintype "passive"))
      (node (ref "U$1") (pin "21") (pinfunction "VCC_21") (pintype "bidirectional"))
      (node (ref "U1") (pin "9") (pinfunction "VLS_9") (pintype "bidirectional"))
    )
    (net (code "54") (name "unconnected-(JP1-Pad2)") (class "Default")
      (node (ref "JP1") (pin "2") (pinfunction "2_2") (pintype "passive"))
    )
    (net (code "55") (name "unconnected-(JP1-Pad5)") (class "Default")
      (node (ref "JP1") (pin "5") (pinfunction "5_5") (pintype "passive"))
    )
    (net (code "56") (name "unconnected-(JP1-Pad9)") (class "Default")
      (node (ref "JP1") (pin "9") (pinfunction "9_9") (pintype "passive"))
    )
    (net (code "57") (name "unconnected-(JP2-Pad2)") (class "Default")
      (node (ref "JP2") (pin "2") (pinfunction "2_2") (pintype "passive"))
    )
    (net (code "58") (name "unconnected-(JP2-Pad3)") (class "Default")
      (node (ref "JP2") (pin "3") (pinfunction "3_3") (pintype "passive"))
    )
    (net (code "59") (name "unconnected-(JP2-Pad4)") (class "Default")
      (node (ref "JP2") (pin "4") (pinfunction "4_4") (pintype "passive"))
    )
    (net (code "60") (name "unconnected-(JP2-Pad5)") (class "Default")
      (node (ref "JP2") (pin "5") (pinfunction "5_5") (pintype "passive"))
    )
    (net (code "61") (name "unconnected-(JP2-Pad6)") (class "Default")
      (node (ref "JP2") (pin "6") (pinfunction "6_6") (pintype "passive"))
    )
    (net (code "62") (name "unconnected-(JP2-Pad7)") (class "Default")
      (node (ref "JP2") (pin "7") (pinfunction "7_7") (pintype "passive"))
    )
    (net (code "63") (name "unconnected-(JP2-Pad8)") (class "Default")
      (node (ref "JP2") (pin "8") (pinfunction "8_8") (pintype "passive"))
    )
    (net (code "64") (name "unconnected-(JP2-Pad9)") (class "Default")
      (node (ref "JP2") (pin "9") (pinfunction "9_9") (pintype "passive"))
    )
    (net (code "65") (name "unconnected-(JP2-Pad10)") (class "Default")
      (node (ref "JP2") (pin "10") (pinfunction "10_10") (pintype "passive"))
    )
    (net (code "66") (name "unconnected-(U$1-2-Pad5)") (class "Default")
      (node (ref "U$1") (pin "5") (pinfunction "2_5") (pintype "bidirectional"))
    )
    (net (code "67") (name "unconnected-(U$1-8-Pad11)") (class "Default")
      (node (ref "U$1") (pin "11") (pinfunction "8_11") (pintype "bidirectional"))
    )
    (net (code "68") (name "unconnected-(U$1-A3-Pad20)") (class "Default")
      (node (ref "U$1") (pin "20") (pinfunction "A3_20") (pintype "bidirectional"))
    )
    (net (code "69") (name "unconnected-(U$1-PadA4)") (class "Default")
      (node (ref "U$1") (pin "A4") (pinfunction "A4_A4") (pintype "bidirectional"))
    )
    (net (code "70") (name "unconnected-(U$1-PadA5)") (class "Default")
      (node (ref "U$1") (pin "A5") (pinfunction "A5_A5") (pintype "bidirectional"))
    )
    (net (code "71") (name "unconnected-(U$1-RST-Pad3)") (class "Default")
      (node (ref "U$1") (pin "3") (pinfunction "RST_3") (pintype "bidirectional"))
    )
    (net (code "72") (name "unconnected-(U$1-RST-Pad22)") (class "Default")
      (node (ref "U$1") (pin "22") (pinfunction "RST_22") (pintype "bidirectional"))
    )
  )
)
